# mainboard.net
KiCad netlist of a schematic drawn in EAGLE
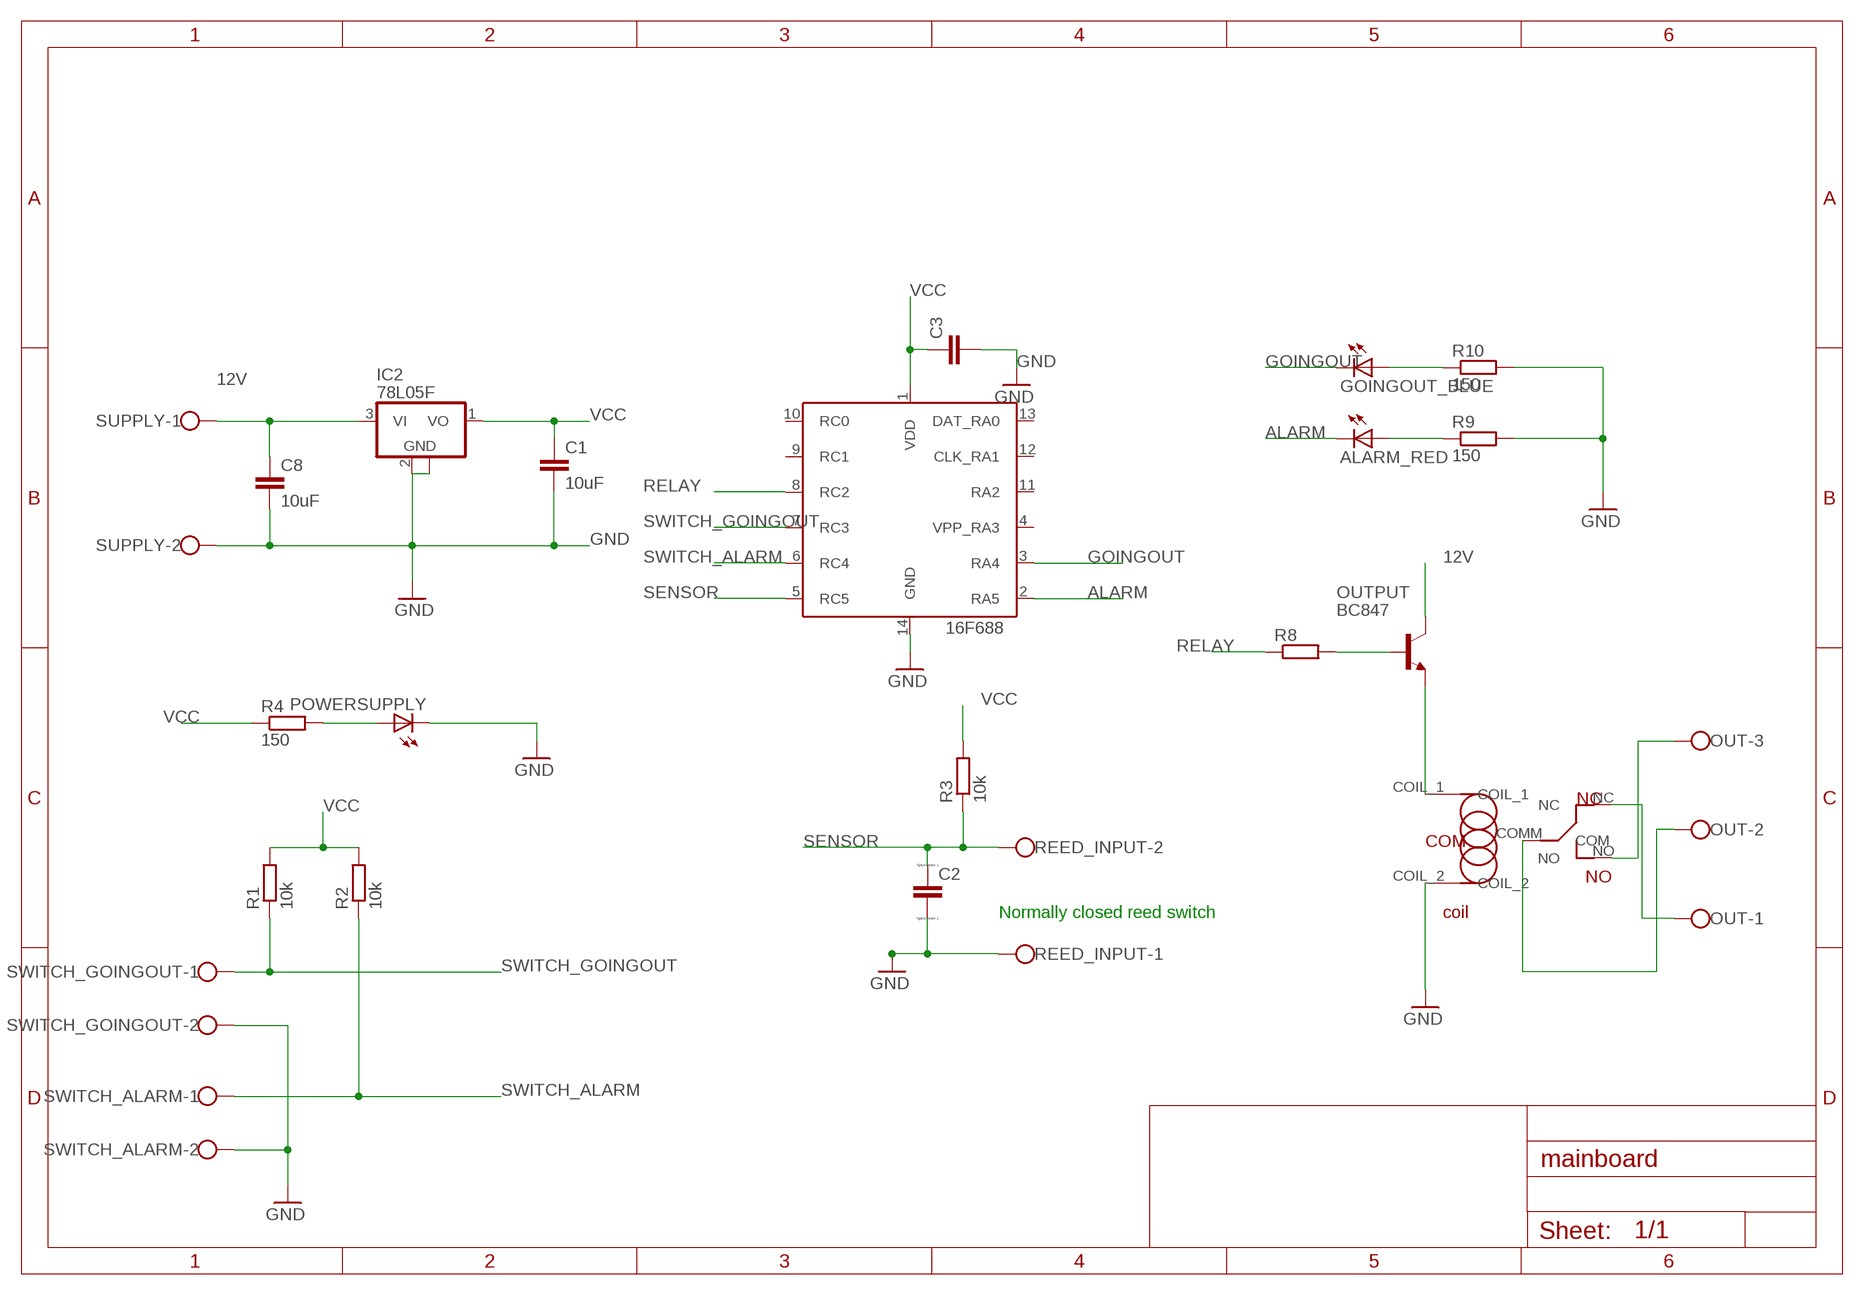
[diagram p0: schematic, sheet 1]

(export (version "E")
  (design (tool "Eeschema 10.0.6"))
  (components
    (comp (ref "ALARM_RED")
      (value "LED5MM")
      (footprint "eagle-import:LED5MM")
      (libsource (lib "eagle-import") (part "LED5MM"))
    )
    (comp (ref "C1")
      (value "10uF")
      (footprint "eagle-import:C0805")
      (libsource (lib "eagle-import") (part "C-EUC0805"))
    )
    (comp (ref "C2")
      (value "CC0603")
      (footprint "eagle-import:C0603")
      (libsource (lib "eagle-import") (part "CC0603"))
    )
    (comp (ref "C3")
      (value "C-EUC0805")
      (footprint "eagle-import:C0805")
      (libsource (lib "eagle-import") (part "C-EUC0805"))
    )
    (comp (ref "C8")
      (value "10uF")
      (footprint "eagle-import:C0805")
      (libsource (lib "eagle-import") (part "C-EUC0805"))
    )
    (comp (ref "GOINGOUT_BLUE")
      (value "LED5MM")
      (footprint "eagle-import:LED5MM")
      (libsource (lib "eagle-import") (part "LED5MM"))
    )
    (comp (ref "IC2")
      (value "78L05F")
      (footprint "eagle-import:SOT89")
      (libsource (lib "eagle-import") (part "78LF05"))
    )
    (comp (ref "OUT")
      (value "W237-103")
      (footprint "eagle-import:W237-103")
      (fields (field (name "MPN") "237-103"))
      (libsource (lib "eagle-import") (part "W237-103"))
    )
    (comp (ref "OUTPUT")
      (value "BC847")
      (footprint "eagle-import:SOT23")
      (libsource (lib "eagle-import") (part "BC847"))
    )
    (comp (ref "POWERSUPPLY")
      (value "LED5MM")
      (footprint "eagle-import:LED5MM")
      (libsource (lib "eagle-import") (part "LED5MM"))
    )
    (comp (ref "R1")
      (value "10k")
      (footprint "eagle-import:R0603")
      (libsource (lib "eagle-import") (part "R-EU_R0603"))
    )
    (comp (ref "R2")
      (value "10k")
      (footprint "eagle-import:R0603")
      (libsource (lib "eagle-import") (part "R-EU_R0603"))
    )
    (comp (ref "R3")
      (value "10k")
      (footprint "eagle-import:R0603")
      (libsource (lib "eagle-import") (part "R-EU_R0603"))
    )
    (comp (ref "R4")
      (value "150")
      (footprint "eagle-import:R0603")
      (libsource (lib "eagle-import") (part "R-EU_R0603"))
    )
    (comp (ref "R8")
      (value "R-EU_R0603")
      (footprint "eagle-import:R0603")
      (libsource (lib "eagle-import") (part "R-EU_R0603"))
    )
    (comp (ref "R9")
      (value "150")
      (footprint "eagle-import:R0603")
      (libsource (lib "eagle-import") (part "R-EU_R0603"))
    )
    (comp (ref "R10")
      (value "150")
      (footprint "eagle-import:R0603")
      (libsource (lib "eagle-import") (part "R-EU_R0603"))
    )
    (comp (ref "REED_INPUT")
      (value "W237-102")
      (footprint "eagle-import:W237-102")
      (fields (field (name "MPN") "237-102"))
      (libsource (lib "eagle-import") (part "W237-102"))
    )
    (comp (ref "SUPPLY")
      (value "W237-102")
      (footprint "eagle-import:W237-102")
      (fields (field (name "MPN") "237-102"))
      (libsource (lib "eagle-import") (part "W237-102"))
    )
    (comp (ref "SWITCH_ALARM")
      (value "W237-102")
      (footprint "eagle-import:W237-102")
      (fields (field (name "MPN") "237-102"))
      (libsource (lib "eagle-import") (part "W237-102"))
    )
    (comp (ref "SWITCH_GOINGOUT")
      (value "W237-102")
      (footprint "eagle-import:W237-102")
      (fields (field (name "MPN") "237-102"))
      (libsource (lib "eagle-import") (part "W237-102"))
    )
    (comp (ref "U$1")
      (value "PIC16F688SOIC14")
      (footprint "eagle-import:SOIC14")
      (libsource (lib "eagle-import") (part "PIC16F688SOIC14"))
    )
    (comp (ref "U$2")
      (value "JQC-3FC_RELAY")
      (footprint "eagle-import:JQC-3FC")
      (libsource (lib "eagle-import") (part "JQC-3FC_RELAY"))
    )
  )
  (nets
    (net (code "1") (name "/12V") (class "Default")
      (node (ref "C8") (pin "1") (pinfunction "1_1") (pintype "passive"))
      (node (ref "IC2") (pin "3") (pinfunction "VI_3") (pintype "input"))
      (node (ref "OUTPUT") (pin "3") (pinfunction "C_3") (pintype "passive"))
      (node (ref "SUPPLY") (pin "1") (pinfunction "KL_1") (pintype "passive"))
    )
    (net (code "2") (name "/ALARM") (class "Default")
      (node (ref "ALARM_RED") (pin "K") (pinfunction "C_K") (pintype "passive"))
      (node (ref "U$1") (pin "2") (pinfunction "RA5_2") (pintype "passive"))
    )
    (net (code "3") (name "/GOINGOUT") (class "Default")
      (node (ref "GOINGOUT_BLUE") (pin "K") (pinfunction "C_K") (pintype "passive"))
      (node (ref "U$1") (pin "3") (pinfunction "RA4_3") (pintype "passive"))
    )
    (net (code "4") (name "/RELAY") (class "Default")
      (node (ref "R8") (pin "1") (pinfunction "1_1") (pintype "passive"))
      (node (ref "U$1") (pin "8") (pinfunction "RC2_8") (pintype "passive"))
    )
    (net (code "5") (name "/SENSOR") (class "Default")
      (node (ref "C2") (pin "1") (pinfunction "1_1") (pintype "passive"))
      (node (ref "R3") (pin "1") (pinfunction "1_1") (pintype "passive"))
      (node (ref "REED_INPUT") (pin "2") (pinfunction "KL_2") (pintype "passive"))
      (node (ref "U$1") (pin "5") (pinfunction "RC5_5") (pintype "passive"))
    )
    (net (code "6") (name "/SWITCH_ALARM") (class "Default")
      (node (ref "R2") (pin "1") (pinfunction "1_1") (pintype "passive"))
      (node (ref "SWITCH_ALARM") (pin "1") (pinfunction "KL_1") (pintype "passive"))
      (node (ref "U$1") (pin "6") (pinfunction "RC4_6") (pintype "passive"))
    )
    (net (code "7") (name "/SWITCH_GOINGOUT") (class "Default")
      (node (ref "R1") (pin "1") (pinfunction "1_1") (pintype "passive"))
      (node (ref "SWITCH_GOINGOUT") (pin "1") (pinfunction "KL_1") (pintype "passive"))
      (node (ref "U$1") (pin "7") (pinfunction "RC3_7") (pintype "passive"))
    )
    (net (code "8") (name "/VCC") (class "Default")
      (node (ref "C1") (pin "1") (pinfunction "1_1") (pintype "passive"))
      (node (ref "C3") (pin "1") (pinfunction "1_1") (pintype "passive"))
      (node (ref "IC2") (pin "1") (pinfunction "VO_1") (pintype "passive"))
      (node (ref "R1") (pin "2") (pinfunction "2_2") (pintype "passive"))
      (node (ref "R2") (pin "2") (pinfunction "2_2") (pintype "passive"))
      (node (ref "R3") (pin "2") (pinfunction "2_2") (pintype "passive"))
      (node (ref "R4") (pin "1") (pinfunction "1_1") (pintype "passive"))
      (node (ref "U$1") (pin "1") (pinfunction "VDD_1") (pintype "passive"))
    )
    (net (code "9") (name "GND") (class "Default")
      (node (ref "C1") (pin "2") (pinfunction "2_2") (pintype "passive"))
      (node (ref "C2") (pin "2") (pinfunction "2_2") (pintype "passive"))
      (node (ref "C3") (pin "2") (pinfunction "2_2") (pintype "passive"))
      (node (ref "C8") (pin "2") (pinfunction "2_2") (pintype "passive"))
      (node (ref "IC2") (pin "2") (pinfunction "GND_2") (pintype "passive"))
      (node (ref "IC2") (pin "2@1") (pinfunction "GND_2@1") (pintype "passive"))
      (node (ref "POWERSUPPLY") (pin "K") (pinfunction "C_K") (pintype "passive"))
      (node (ref "R10") (pin "2") (pinfunction "2_2") (pintype "passive"))
      (node (ref "R9") (pin "2") (pinfunction "2_2") (pintype "passive"))
      (node (ref "REED_INPUT") (pin "1") (pinfunction "KL_1") (pintype "passive"))
      (node (ref "SUPPLY") (pin "2") (pinfunction "KL_2") (pintype "passive"))
      (node (ref "SWITCH_ALARM") (pin "2") (pinfunction "KL_2") (pintype "passive"))
      (node (ref "SWITCH_GOINGOUT") (pin "2") (pinfunction "KL_2") (pintype "passive"))
      (node (ref "U$1") (pin "14") (pinfunction "GND_14") (pintype "passive"))
      (node (ref "U$2") (pin "COIL_2") (pinfunction "COIL_2_COIL_2") (pintype "bidirectional"))
    )
    (net (code "10") (name "Net-(ALARM_RED-PadA)") (class "Default")
      (node (ref "ALARM_RED") (pin "A") (pinfunction "A_A") (pintype "passive"))
      (node (ref "R9") (pin "1") (pinfunction "1_1") (pintype "passive"))
    )
    (net (code "11") (name "Net-(GOINGOUT_BLUE-PadA)") (class "Default")
      (node (ref "GOINGOUT_BLUE") (pin "A") (pinfunction "A_A") (pintype "passive"))
      (node (ref "R10") (pin "1") (pinfunction "1_1") (pintype "passive"))
    )
    (net (code "12") (name "Net-(OUTA-KL)") (class "Default")
      (node (ref "OUT") (pin "1") (pinfunction "KL_1") (pintype "passive"))
      (node (ref "U$2") (pin "NC") (pinfunction "NC_NC") (pintype "bidirectional"))
    )
    (net (code "13") (name "Net-(OUTB-KL)") (class "Default")
      (node (ref "OUT") (pin "2") (pinfunction "KL_2") (pintype "passive"))
      (node (ref "U$2") (pin "COMM") (pinfunction "COM_COMM") (pintype "bidirectional"))
    )
    (net (code "14") (name "Net-(OUTC-KL)") (class "Default")
      (node (ref "OUT") (pin "3") (pinfunction "KL_3") (pintype "passive"))
      (node (ref "U$2") (pin "NO") (pinfunction "NO_NO") (pintype "bidirectional"))
    )
    (net (code "15") (name "Net-(OUTPUT-B)") (class "Default")
      (node (ref "OUTPUT") (pin "1") (pinfunction "B_1") (pintype "passive"))
      (node (ref "R8") (pin "2") (pinfunction "2_2") (pintype "passive"))
    )
    (net (code "16") (name "Net-(OUTPUT-E)") (class "Default")
      (node (ref "OUTPUT") (pin "2") (pinfunction "E_2") (pintype "passive"))
      (node (ref "U$2") (pin "COIL_1") (pinfunction "COIL_1_COIL_1") (pintype "bidirectional"))
    )
    (net (code "17") (name "Net-(POWERSUPPLY-PadA)") (class "Default")
      (node (ref "POWERSUPPLY") (pin "A") (pinfunction "A_A") (pintype "passive"))
      (node (ref "R4") (pin "2") (pinfunction "2_2") (pintype "passive"))
    )
    (net (code "18") (name "unconnected-(U$1-CLK_RA1-Pad12)") (class "Default")
      (node (ref "U$1") (pin "12") (pinfunction "CLK_RA1_12") (pintype "passive"))
    )
    (net (code "19") (name "unconnected-(U$1-DAT_RA0-Pad13)") (class "Default")
      (node (ref "U$1") (pin "13") (pinfunction "DAT_RA0_13") (pintype "passive"))
    )
    (net (code "20") (name "unconnected-(U$1-RA2-Pad11)") (class "Default")
      (node (ref "U$1") (pin "11") (pinfunction "RA2_11") (pintype "passive"))
    )
    (net (code "21") (name "unconnected-(U$1-RC0-Pad10)") (class "Default")
      (node (ref "U$1") (pin "10") (pinfunction "RC0_10") (pintype "passive"))
    )
    (net (code "22") (name "unconnected-(U$1-RC1-Pad9)") (class "Default")
      (node (ref "U$1") (pin "9") (pinfunction "RC1_9") (pintype "passive"))
    )
    (net (code "23") (name "unconnected-(U$1-VPP_RA3-Pad4)") (class "Default")
      (node (ref "U$1") (pin "4") (pinfunction "VPP_RA3_4") (pintype "passive"))
    )
  )
)
